# IO-Linky6362_rev1_0.net
KiCad netlist of a schematic drawn in EAGLE
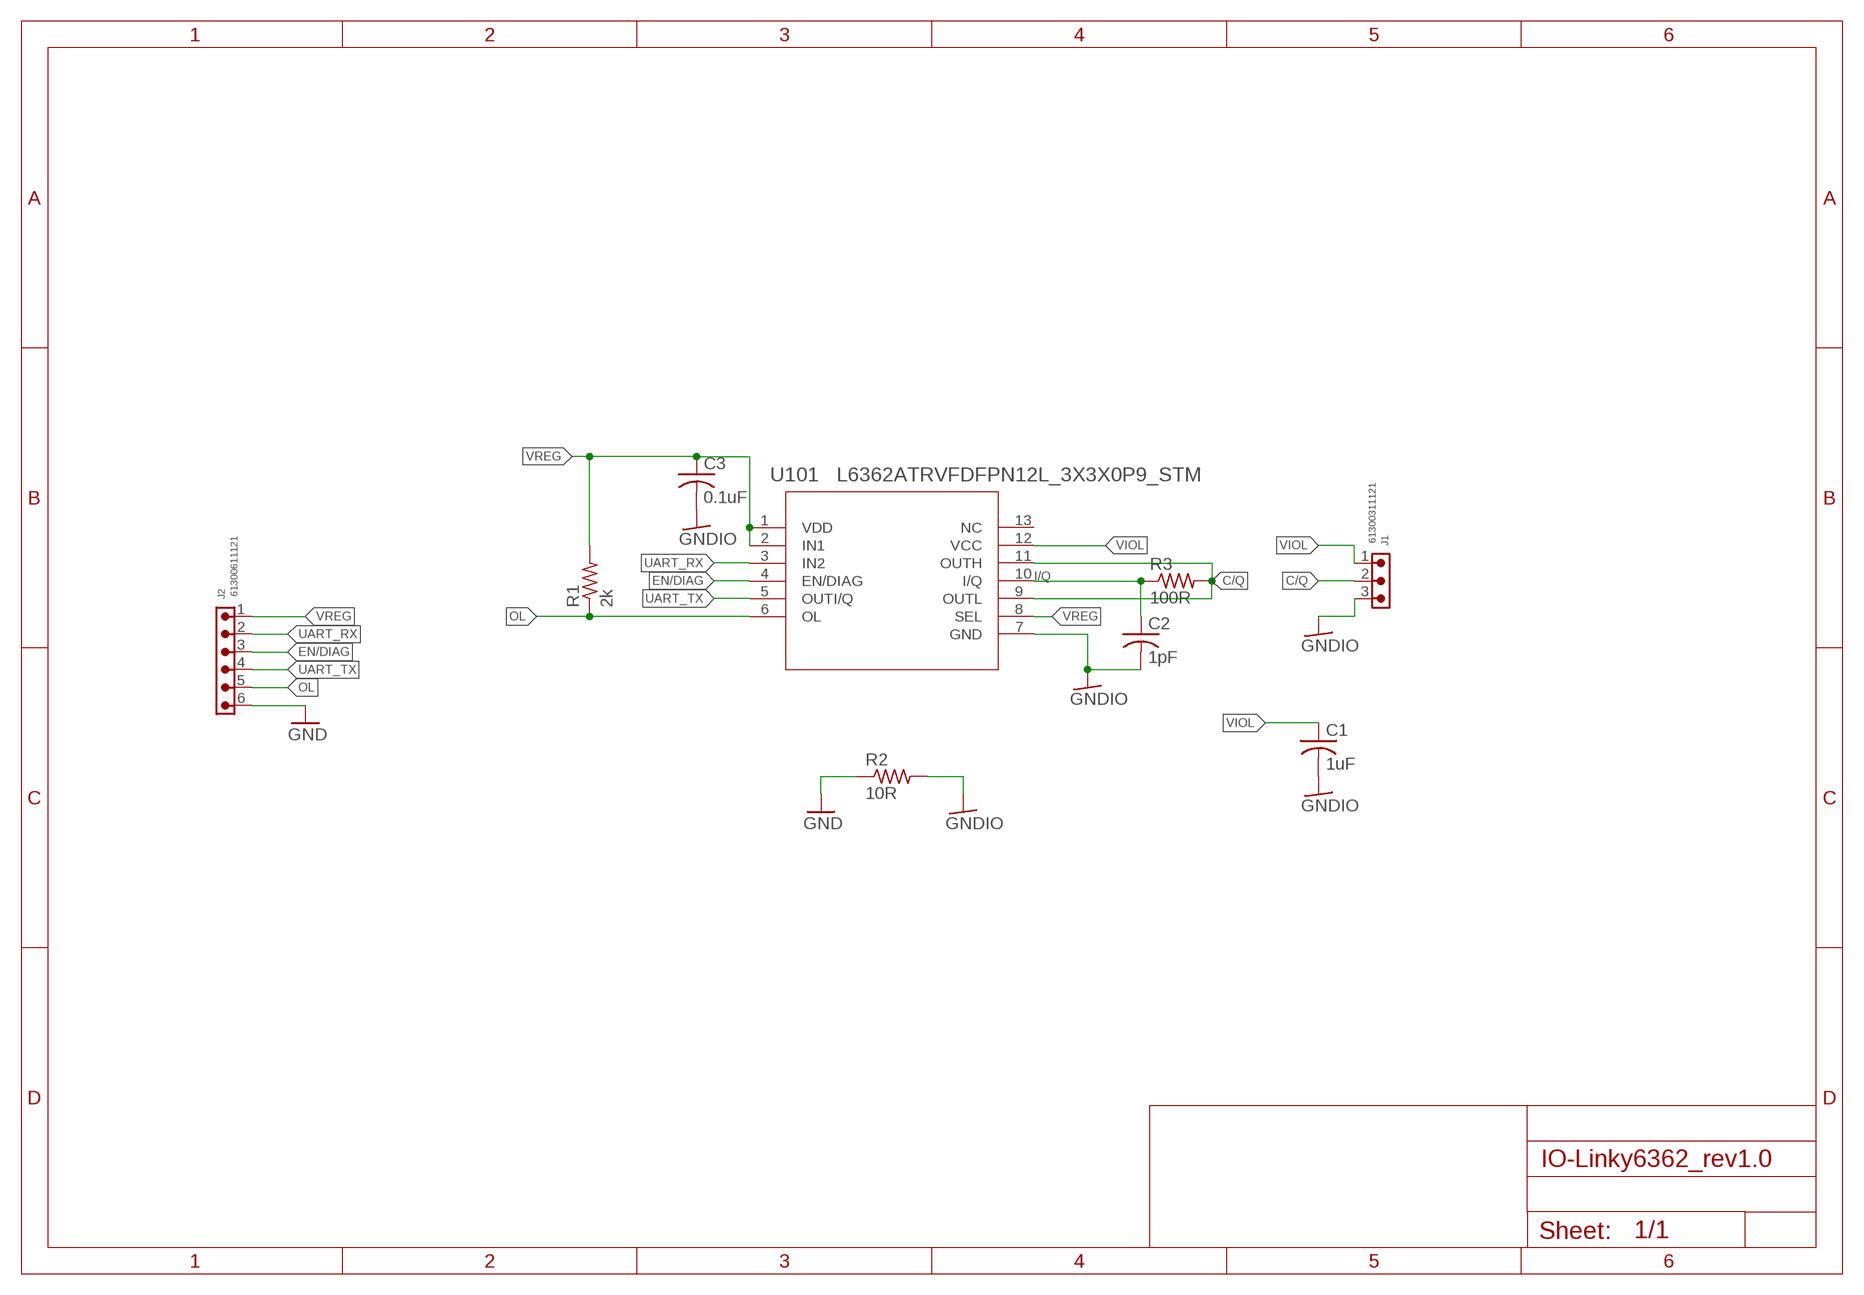
[diagram p0: schematic, sheet 1]

(export (version "E")
  (design (tool "Eeschema 10.0.6"))
  (components
    (comp (ref "C1")
      (value "1uF")
      (footprint "eagle-import:C0603K")
      (libsource (lib "eagle-import") (part "C-USC0603K"))
    )
    (comp (ref "C2")
      (value "1pF")
      (footprint "eagle-import:C0603K")
      (libsource (lib "eagle-import") (part "C-USC0603K"))
    )
    (comp (ref "C3")
      (value "0.1uF")
      (footprint "eagle-import:C0603K")
      (libsource (lib "eagle-import") (part "C-USC0603K"))
    )
    (comp (ref "J1")
      (value "61300311121")
      (footprint "eagle-import:61300311121")
      (libsource (lib "eagle-import") (part "6130XX11121_61300311121"))
    )
    (comp (ref "J2")
      (value "61300611121")
      (footprint "eagle-import:61300611121")
      (libsource (lib "eagle-import") (part "6130XX11121_61300611121"))
    )
    (comp (ref "R1")
      (value "2k")
      (footprint "eagle-import:R0603")
      (libsource (lib "eagle-import") (part "R-US_R0603"))
    )
    (comp (ref "R2")
      (value "10R")
      (footprint "eagle-import:R0603")
      (libsource (lib "eagle-import") (part "R-US_R0603"))
    )
    (comp (ref "R3")
      (value "100R")
      (footprint "eagle-import:R0603")
      (libsource (lib "eagle-import") (part "R-US_R0603"))
    )
    (comp (ref "U101")
      (value "L6362ATRVFDFPN12L_3X3X0P9_STM")
      (footprint "eagle-import:VFDFPN12L_3X3X0P9_STM")
      (fields
        (field (name "MANUFACTURER_PART_NUMBER") "L6362ATR")
        (field (name "COPYRIGHT") "Copyright (C) 2024 Ultra Librarian. All rights reserved.")
      )
      (libsource (lib "eagle-import") (part "L6362ATRVFDFPN12L_3X3X0P9_STM"))
    )
  )
  (nets
    (net (code "1") (name "/I{slash}Q") (class "Default")
      (node (ref "C2") (pin "1") (pinfunction "1_1") (pintype "passive"))
      (node (ref "R3") (pin "1") (pinfunction "1_1") (pintype "passive"))
      (node (ref "U101") (pin "10") (pinfunction "I/Q_10") (pintype "input"))
    )
    (net (code "2") (name "C{slash}Q") (class "Default")
      (node (ref "J1") (pin "2") (pinfunction "2_2") (pintype "passive"))
      (node (ref "R3") (pin "2") (pinfunction "2_2") (pintype "passive"))
      (node (ref "U101") (pin "11") (pinfunction "OUTH_11") (pintype "output"))
      (node (ref "U101") (pin "9") (pinfunction "OUTL_9") (pintype "output"))
    )
    (net (code "3") (name "EN{slash}DIAG") (class "Default")
      (node (ref "J2") (pin "3") (pinfunction "3_3") (pintype "passive"))
      (node (ref "U101") (pin "4") (pinfunction "EN/DIAG_4") (pintype "bidirectional"))
    )
    (net (code "4") (name "GND") (class "Default")
      (node (ref "J2") (pin "6") (pinfunction "6_6") (pintype "passive"))
      (node (ref "R2") (pin "1") (pinfunction "1_1") (pintype "passive"))
    )
    (net (code "5") (name "GNDIO") (class "Default")
      (node (ref "C1") (pin "2") (pinfunction "2_2") (pintype "passive"))
      (node (ref "C2") (pin "2") (pinfunction "2_2") (pintype "passive"))
      (node (ref "C3") (pin "2") (pinfunction "2_2") (pintype "passive"))
      (node (ref "J1") (pin "3") (pinfunction "3_3") (pintype "passive"))
      (node (ref "R2") (pin "2") (pinfunction "2_2") (pintype "passive"))
      (node (ref "U101") (pin "7") (pinfunction "GND_7") (pintype "passive"))
    )
    (net (code "6") (name "OL") (class "Default")
      (node (ref "J2") (pin "5") (pinfunction "5_5") (pintype "passive"))
      (node (ref "R1") (pin "1") (pinfunction "1_1") (pintype "passive"))
      (node (ref "U101") (pin "6") (pinfunction "OL_6") (pintype "output"))
    )
    (net (code "7") (name "UART_RX") (class "Default")
      (node (ref "J2") (pin "2") (pinfunction "2_2") (pintype "passive"))
      (node (ref "U101") (pin "3") (pinfunction "IN2_3") (pintype "input"))
    )
    (net (code "8") (name "UART_TX") (class "Default")
      (node (ref "J2") (pin "4") (pinfunction "4_4") (pintype "passive"))
      (node (ref "U101") (pin "5") (pinfunction "OUTI/Q_5") (pintype "output"))
    )
    (net (code "9") (name "VIOL") (class "Default")
      (node (ref "C1") (pin "1") (pinfunction "1_1") (pintype "passive"))
      (node (ref "J1") (pin "1") (pinfunction "1_1") (pintype "passive"))
      (node (ref "U101") (pin "12") (pinfunction "VCC_12") (pintype "power_in"))
    )
    (net (code "10") (name "VREG") (class "Default")
      (node (ref "C3") (pin "1") (pinfunction "1_1") (pintype "passive"))
      (node (ref "J2") (pin "1") (pinfunction "1_1") (pintype "passive"))
      (node (ref "R1") (pin "2") (pinfunction "2_2") (pintype "passive"))
      (node (ref "U101") (pin "1") (pinfunction "VDD_1") (pintype "output"))
      (node (ref "U101") (pin "2") (pinfunction "IN1_2") (pintype "input"))
      (node (ref "U101") (pin "8") (pinfunction "SEL_8") (pintype "input"))
    )
    (net (code "11") (name "unconnected-(U101-NC-Pad13)") (class "Default")
      (node (ref "U101") (pin "13") (pinfunction "NC_13") (pintype "no_connect"))
    )
  )
)
